# BSPD_3.net
KiCad netlist of a schematic drawn in EAGLE
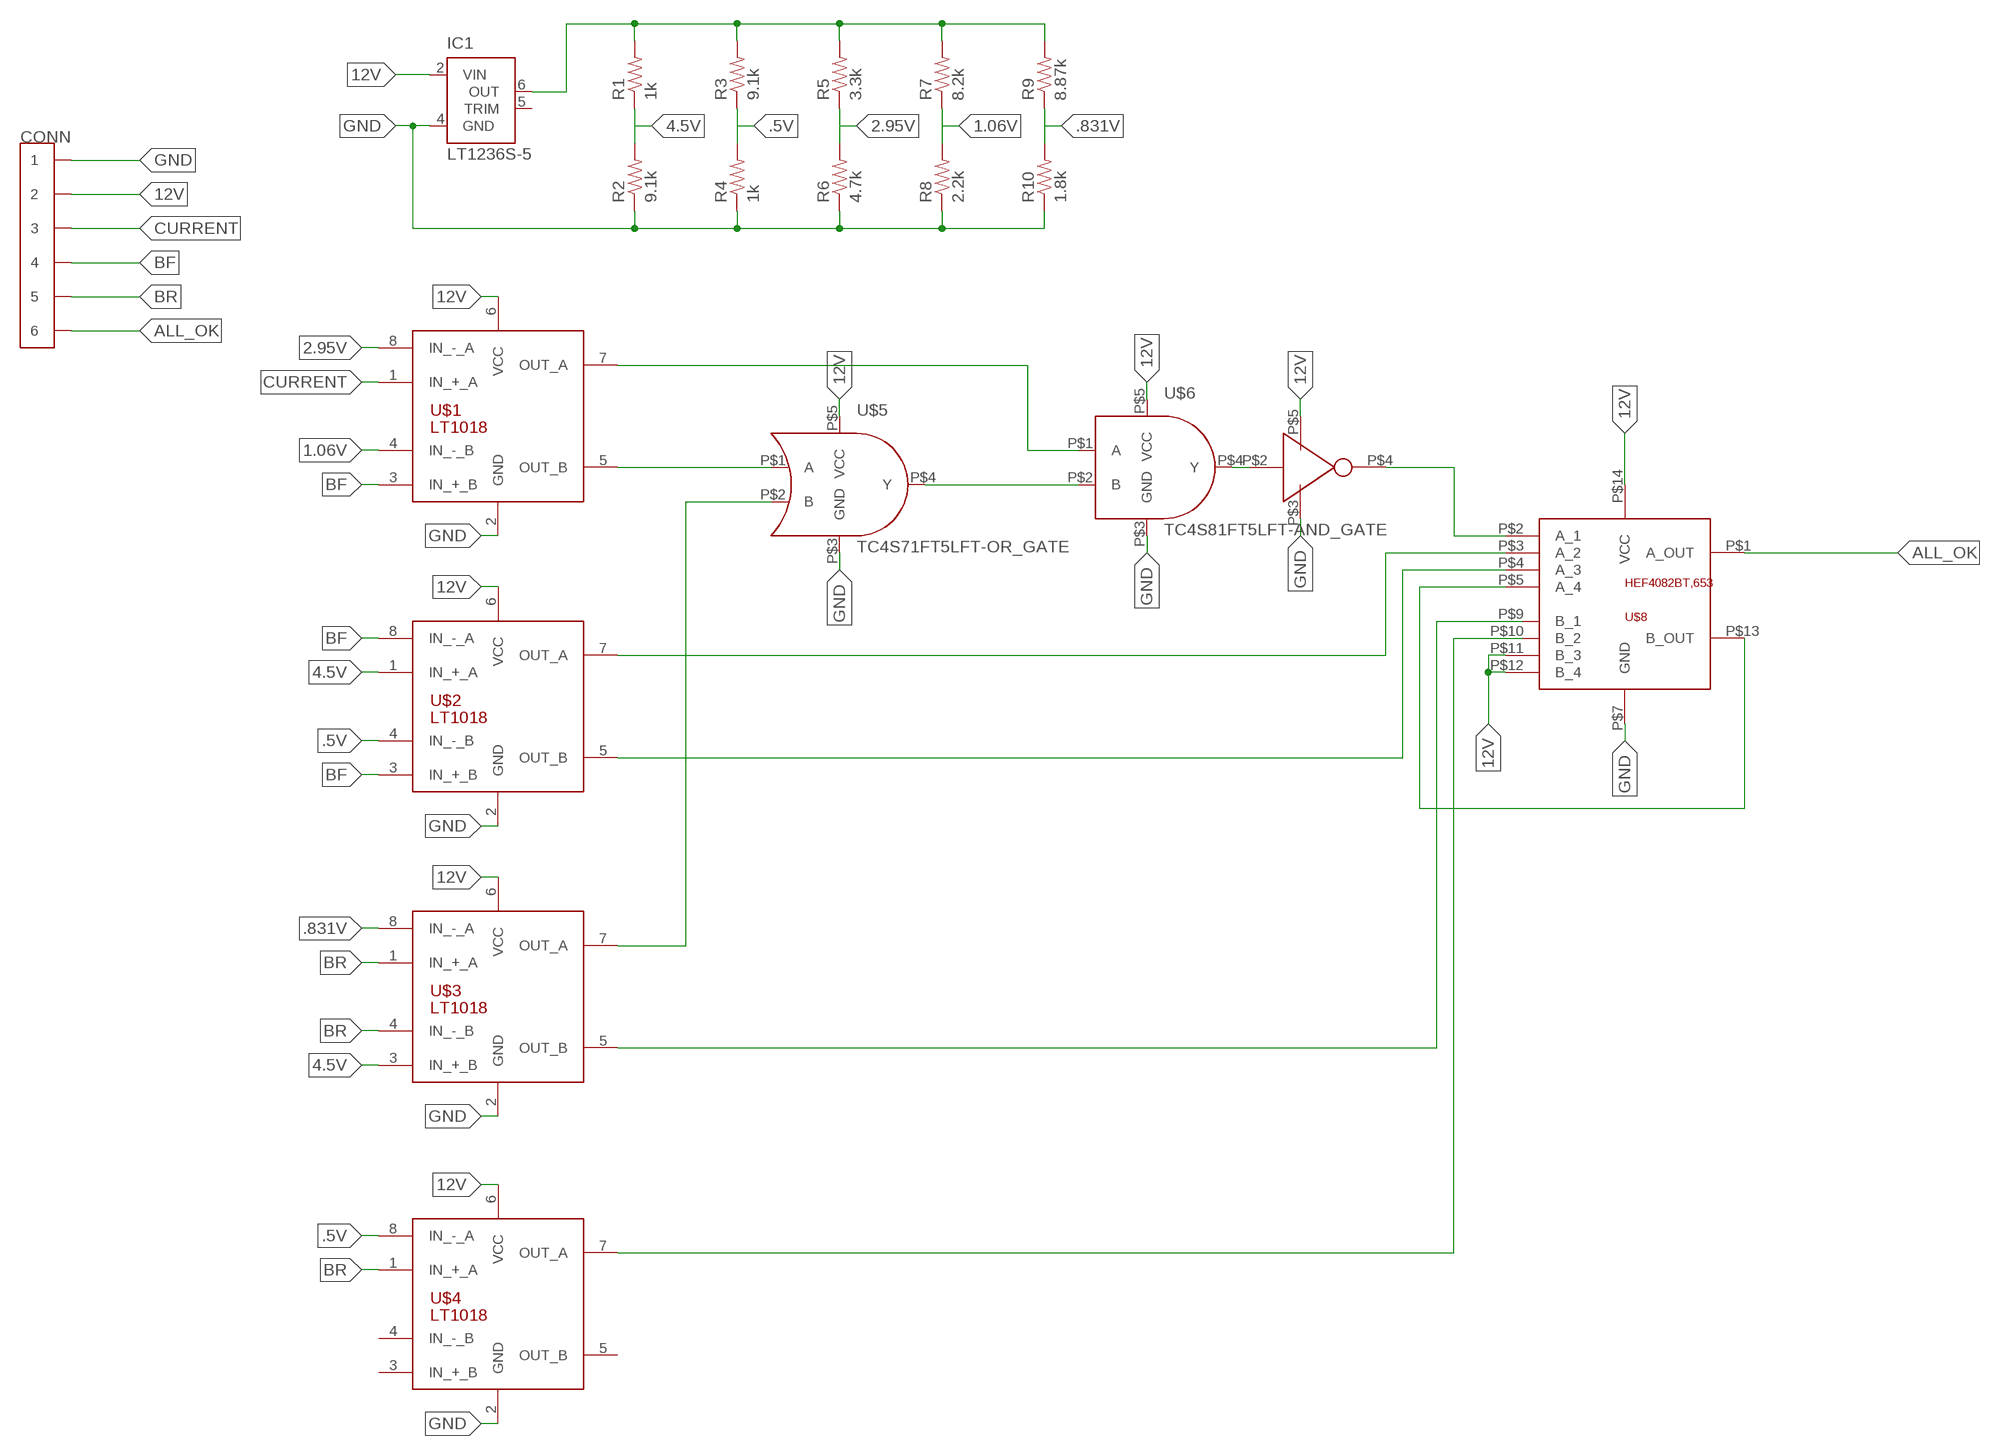
[diagram p0: schematic, sheet 1]

(export (version "E")
  (design (tool "Eeschema 10.0.6"))
  (components
    (comp (ref "CONN")
      (value "CONN_6")
      (footprint "eagle-import:CONNECTOR_6")
      (libsource (lib "eagle-import") (part "CONN_6"))
    )
    (comp (ref "IC1")
      (value "LT1236S-5")
      (footprint "eagle-import:SOIC8")
      (libsource (lib "eagle-import") (part "LT1236?S-5"))
    )
    (comp (ref "R1")
      (value "1k")
      (footprint "eagle-import:0603-RES")
      (libsource (lib "eagle-import") (part "RESISTOR0603"))
    )
    (comp (ref "R2")
      (value "9.1k")
      (footprint "eagle-import:0603-RES")
      (libsource (lib "eagle-import") (part "RESISTOR0603"))
    )
    (comp (ref "R3")
      (value "9.1k")
      (footprint "eagle-import:0603-RES")
      (libsource (lib "eagle-import") (part "RESISTOR0603"))
    )
    (comp (ref "R4")
      (value "1k")
      (footprint "eagle-import:0603-RES")
      (libsource (lib "eagle-import") (part "RESISTOR0603"))
    )
    (comp (ref "R5")
      (value "3.3k")
      (footprint "eagle-import:0603-RES")
      (libsource (lib "eagle-import") (part "RESISTOR0603"))
    )
    (comp (ref "R6")
      (value "4.7k")
      (footprint "eagle-import:0603-RES")
      (libsource (lib "eagle-import") (part "RESISTOR0603"))
    )
    (comp (ref "R7")
      (value "8.2k")
      (footprint "eagle-import:0603-RES")
      (libsource (lib "eagle-import") (part "RESISTOR0603"))
    )
    (comp (ref "R8")
      (value "2.2k")
      (footprint "eagle-import:0603-RES")
      (libsource (lib "eagle-import") (part "RESISTOR0603"))
    )
    (comp (ref "R9")
      (value "8.87k")
      (footprint "eagle-import:0603-RES")
      (libsource (lib "eagle-import") (part "RESISTOR0603"))
    )
    (comp (ref "R10")
      (value "1.8k")
      (footprint "eagle-import:0603-RES")
      (libsource (lib "eagle-import") (part "RESISTOR0603"))
    )
    (comp (ref "U$1")
      (value "LT1018")
      (footprint "eagle-import:SOIC8")
      (libsource (lib "eagle-import") (part "LT1018"))
    )
    (comp (ref "U$2")
      (value "LT1018")
      (footprint "eagle-import:SOIC8")
      (libsource (lib "eagle-import") (part "LT1018"))
    )
    (comp (ref "U$3")
      (value "LT1018")
      (footprint "eagle-import:SOIC8")
      (libsource (lib "eagle-import") (part "LT1018"))
    )
    (comp (ref "U$4")
      (value "LT1018")
      (footprint "eagle-import:SOIC8")
      (libsource (lib "eagle-import") (part "LT1018"))
    )
    (comp (ref "U$5")
      (value "TC4S71FT5LFT-OR_GATE")
      (footprint "eagle-import:SSOP5-P-0.95")
      (libsource (lib "eagle-import") (part "TC4S71FT5LFT-OR_GATE"))
    )
    (comp (ref "U$6")
      (value "TC4S81FT5LFT-AND_GATE")
      (footprint "eagle-import:SSOP5-P-0.95")
      (libsource (lib "eagle-import") (part "TC4S81FT5LFT-AND_GATE"))
    )
    (comp (ref "U$7")
      (value "TC4S69F(TE85L,F)")
      (footprint "eagle-import:SSOP5-P-0.95")
      (libsource (lib "eagle-import") (part "TC4S69F(TE85L,F)"))
    )
    (comp (ref "U$8")
      (value "HEF4082BT,653")
      (footprint "eagle-import:NXP_14_SOIC")
      (libsource (lib "eagle-import") (part "HEF4082BT,653"))
    )
  )
  (nets
    (net (code "1") (name ".5V") (class "Default")
      (node (ref "R3") (pin "1") (pinfunction "1_1") (pintype "passive"))
      (node (ref "R4") (pin "2") (pinfunction "2_2") (pintype "passive"))
      (node (ref "U$2") (pin "4") (pinfunction "IN_-_B_4") (pintype "input"))
      (node (ref "U$4") (pin "8") (pinfunction "IN_-_A_8") (pintype "input"))
    )
    (net (code "2") (name ".831V") (class "Default")
      (node (ref "R10") (pin "2") (pinfunction "2_2") (pintype "passive"))
      (node (ref "R9") (pin "1") (pinfunction "1_1") (pintype "passive"))
      (node (ref "U$3") (pin "8") (pinfunction "IN_-_A_8") (pintype "input"))
    )
    (net (code "3") (name "1.06V") (class "Default")
      (node (ref "R7") (pin "1") (pinfunction "1_1") (pintype "passive"))
      (node (ref "R8") (pin "2") (pinfunction "2_2") (pintype "passive"))
      (node (ref "U$1") (pin "4") (pinfunction "IN_-_B_4") (pintype "input"))
    )
    (net (code "4") (name "2.95V") (class "Default")
      (node (ref "R5") (pin "1") (pinfunction "1_1") (pintype "passive"))
      (node (ref "R6") (pin "2") (pinfunction "2_2") (pintype "passive"))
      (node (ref "U$1") (pin "8") (pinfunction "IN_-_A_8") (pintype "input"))
    )
    (net (code "5") (name "4.5V") (class "Default")
      (node (ref "R1") (pin "1") (pinfunction "1_1") (pintype "passive"))
      (node (ref "R2") (pin "2") (pinfunction "2_2") (pintype "passive"))
      (node (ref "U$2") (pin "1") (pinfunction "IN_+_A_1") (pintype "input"))
      (node (ref "U$3") (pin "3") (pinfunction "IN_+_B_3") (pintype "input"))
    )
    (net (code "6") (name "12V") (class "Default")
      (node (ref "CONN") (pin "3") (pinfunction "2_3") (pintype "bidirectional"))
      (node (ref "CONN") (pin "4") (pinfunction "2_4") (pintype "bidirectional"))
      (node (ref "IC1") (pin "2") (pinfunction "VIN_2") (pintype "input"))
      (node (ref "U$1") (pin "6") (pinfunction "VCC_6") (pintype "power_in"))
      (node (ref "U$2") (pin "6") (pinfunction "VCC_6") (pintype "power_in"))
      (node (ref "U$3") (pin "6") (pinfunction "VCC_6") (pintype "power_in"))
      (node (ref "U$4") (pin "6") (pinfunction "VCC_6") (pintype "power_in"))
      (node (ref "U$5") (pin "P$5") (pinfunction "VCC_P$5") (pintype "bidirectional"))
      (node (ref "U$6") (pin "P$5") (pinfunction "VCC_P$5") (pintype "bidirectional"))
      (node (ref "U$7") (pin "P$5") (pinfunction "VCC_P$5") (pintype "power_in"))
      (node (ref "U$8") (pin "P$11") (pinfunction "B_3_P$11") (pintype "open_collector"))
      (node (ref "U$8") (pin "P$12") (pinfunction "B_4_P$12") (pintype "open_collector"))
      (node (ref "U$8") (pin "P$14") (pinfunction "VCC_P$14") (pintype "power_in"))
    )
    (net (code "7") (name "ALL_OK") (class "Default")
      (node (ref "CONN") (pin "11") (pinfunction "6_11") (pintype "bidirectional"))
      (node (ref "CONN") (pin "12") (pinfunction "6_12") (pintype "bidirectional"))
      (node (ref "U$8") (pin "P$1") (pinfunction "A_OUT_P$1") (pintype "output"))
    )
    (net (code "8") (name "BF") (class "Default")
      (node (ref "CONN") (pin "7") (pinfunction "4_7") (pintype "bidirectional"))
      (node (ref "CONN") (pin "8") (pinfunction "4_8") (pintype "bidirectional"))
      (node (ref "U$1") (pin "3") (pinfunction "IN_+_B_3") (pintype "input"))
      (node (ref "U$2") (pin "3") (pinfunction "IN_+_B_3") (pintype "input"))
      (node (ref "U$2") (pin "8") (pinfunction "IN_-_A_8") (pintype "input"))
    )
    (net (code "9") (name "BR") (class "Default")
      (node (ref "CONN") (pin "10") (pinfunction "5_10") (pintype "bidirectional"))
      (node (ref "CONN") (pin "9") (pinfunction "5_9") (pintype "bidirectional"))
      (node (ref "U$3") (pin "1") (pinfunction "IN_+_A_1") (pintype "input"))
      (node (ref "U$3") (pin "4") (pinfunction "IN_-_B_4") (pintype "input"))
      (node (ref "U$4") (pin "1") (pinfunction "IN_+_A_1") (pintype "input"))
    )
    (net (code "10") (name "CURRENT") (class "Default")
      (node (ref "CONN") (pin "5") (pinfunction "3_5") (pintype "bidirectional"))
      (node (ref "CONN") (pin "6") (pinfunction "3_6") (pintype "bidirectional"))
      (node (ref "U$1") (pin "1") (pinfunction "IN_+_A_1") (pintype "input"))
    )
    (net (code "11") (name "GND") (class "Default")
      (node (ref "CONN") (pin "1") (pinfunction "1_1") (pintype "bidirectional"))
      (node (ref "CONN") (pin "2") (pinfunction "1_2") (pintype "bidirectional"))
      (node (ref "IC1") (pin "4") (pinfunction "GND_4") (pintype "power_in"))
      (node (ref "R10") (pin "1") (pinfunction "1_1") (pintype "passive"))
      (node (ref "R2") (pin "1") (pinfunction "1_1") (pintype "passive"))
      (node (ref "R4") (pin "1") (pinfunction "1_1") (pintype "passive"))
      (node (ref "R6") (pin "1") (pinfunction "1_1") (pintype "passive"))
      (node (ref "R8") (pin "1") (pinfunction "1_1") (pintype "passive"))
      (node (ref "U$1") (pin "2") (pinfunction "GND_2") (pintype "power_in"))
      (node (ref "U$2") (pin "2") (pinfunction "GND_2") (pintype "power_in"))
      (node (ref "U$3") (pin "2") (pinfunction "GND_2") (pintype "power_in"))
      (node (ref "U$4") (pin "2") (pinfunction "GND_2") (pintype "power_in"))
      (node (ref "U$5") (pin "P$3") (pinfunction "GND_P$3") (pintype "bidirectional"))
      (node (ref "U$6") (pin "P$3") (pinfunction "GND_P$3") (pintype "bidirectional"))
      (node (ref "U$7") (pin "P$3") (pinfunction "GND_P$3") (pintype "power_in"))
      (node (ref "U$8") (pin "P$7") (pinfunction "GND_P$7") (pintype "power_in"))
    )
    (net (code "12") (name "Net-(IC1-OUT)") (class "Default")
      (node (ref "IC1") (pin "6") (pinfunction "OUT_6") (pintype "input"))
      (node (ref "R1") (pin "2") (pinfunction "2_2") (pintype "passive"))
      (node (ref "R3") (pin "2") (pinfunction "2_2") (pintype "passive"))
      (node (ref "R5") (pin "2") (pinfunction "2_2") (pintype "passive"))
      (node (ref "R7") (pin "2") (pinfunction "2_2") (pintype "passive"))
      (node (ref "R9") (pin "2") (pinfunction "2_2") (pintype "passive"))
    )
    (net (code "13") (name "Net-(U$1-OUT_A)") (class "Default")
      (node (ref "U$1") (pin "7") (pinfunction "OUT_A_7") (pintype "output"))
      (node (ref "U$6") (pin "P$1") (pinfunction "A_P$1") (pintype "bidirectional"))
    )
    (net (code "14") (name "Net-(U$1-OUT_B)") (class "Default")
      (node (ref "U$1") (pin "5") (pinfunction "OUT_B_5") (pintype "output"))
      (node (ref "U$5") (pin "P$1") (pinfunction "A_P$1") (pintype "bidirectional"))
    )
    (net (code "15") (name "Net-(U$2-OUT_A)") (class "Default")
      (node (ref "U$2") (pin "7") (pinfunction "OUT_A_7") (pintype "output"))
      (node (ref "U$8") (pin "P$3") (pinfunction "A_2_P$3") (pintype "open_collector"))
    )
    (net (code "16") (name "Net-(U$2-OUT_B)") (class "Default")
      (node (ref "U$2") (pin "5") (pinfunction "OUT_B_5") (pintype "output"))
      (node (ref "U$8") (pin "P$4") (pinfunction "A_3_P$4") (pintype "open_collector"))
    )
    (net (code "17") (name "Net-(U$3-OUT_A)") (class "Default")
      (node (ref "U$3") (pin "7") (pinfunction "OUT_A_7") (pintype "output"))
      (node (ref "U$5") (pin "P$2") (pinfunction "B_P$2") (pintype "bidirectional"))
    )
    (net (code "18") (name "Net-(U$5-Y)") (class "Default")
      (node (ref "U$5") (pin "P$4") (pinfunction "Y_P$4") (pintype "bidirectional"))
      (node (ref "U$6") (pin "P$2") (pinfunction "B_P$2") (pintype "bidirectional"))
    )
    (net (code "19") (name "Net-(U$6-Y)") (class "Default")
      (node (ref "U$6") (pin "P$4") (pinfunction "Y_P$4") (pintype "bidirectional"))
      (node (ref "U$7") (pin "P$2") (pinfunction "IN_P$2") (pintype "input"))
    )
    (net (code "20") (name "Net-(U$7-OUT)") (class "Default")
      (node (ref "U$7") (pin "P$4") (pinfunction "OUT_P$4") (pintype "output"))
      (node (ref "U$8") (pin "P$2") (pinfunction "A_1_P$2") (pintype "open_collector"))
    )
    (net (code "21") (name "Net-(U$8-A_4)") (class "Default")
      (node (ref "U$8") (pin "P$13") (pinfunction "B_OUT_P$13") (pintype "output"))
      (node (ref "U$8") (pin "P$5") (pinfunction "A_4_P$5") (pintype "open_collector"))
    )
    (net (code "22") (name "unconnected-(IC1-TRIM-Pad5)") (class "Default")
      (node (ref "IC1") (pin "5") (pinfunction "TRIM_5") (pintype "passive"))
    )
    (net (code "23") (name "unconnected-(U$3-OUT_B-Pad5)") (class "Default")
      (node (ref "U$3") (pin "5") (pinfunction "OUT_B_5") (pintype "output"))
    )
    (net (code "24") (name "unconnected-(U$4-IN_+_B-Pad3)") (class "Default")
      (node (ref "U$4") (pin "3") (pinfunction "IN_+_B_3") (pintype "input"))
    )
    (net (code "25") (name "unconnected-(U$4-IN_-_B-Pad4)") (class "Default")
      (node (ref "U$4") (pin "4") (pinfunction "IN_-_B_4") (pintype "input"))
    )
    (net (code "26") (name "unconnected-(U$4-OUT_A-Pad7)") (class "Default")
      (node (ref "U$4") (pin "7") (pinfunction "OUT_A_7") (pintype "output"))
    )
    (net (code "27") (name "unconnected-(U$4-OUT_B-Pad5)") (class "Default")
      (node (ref "U$4") (pin "5") (pinfunction "OUT_B_5") (pintype "output"))
    )
    (net (code "28") (name "unconnected-(U$8-B_1-PadP$9)") (class "Default")
      (node (ref "U$8") (pin "P$9") (pinfunction "B_1_P$9") (pintype "open_collector"))
    )
    (net (code "29") (name "unconnected-(U$8-B_2-PadP$10)") (class "Default")
      (node (ref "U$8") (pin "P$10") (pinfunction "B_2_P$10") (pintype "open_collector"))
    )
  )
)
